# SuperTiny-REV2-Corrected-Stencil.net
KiCad netlist of a schematic drawn in EAGLE
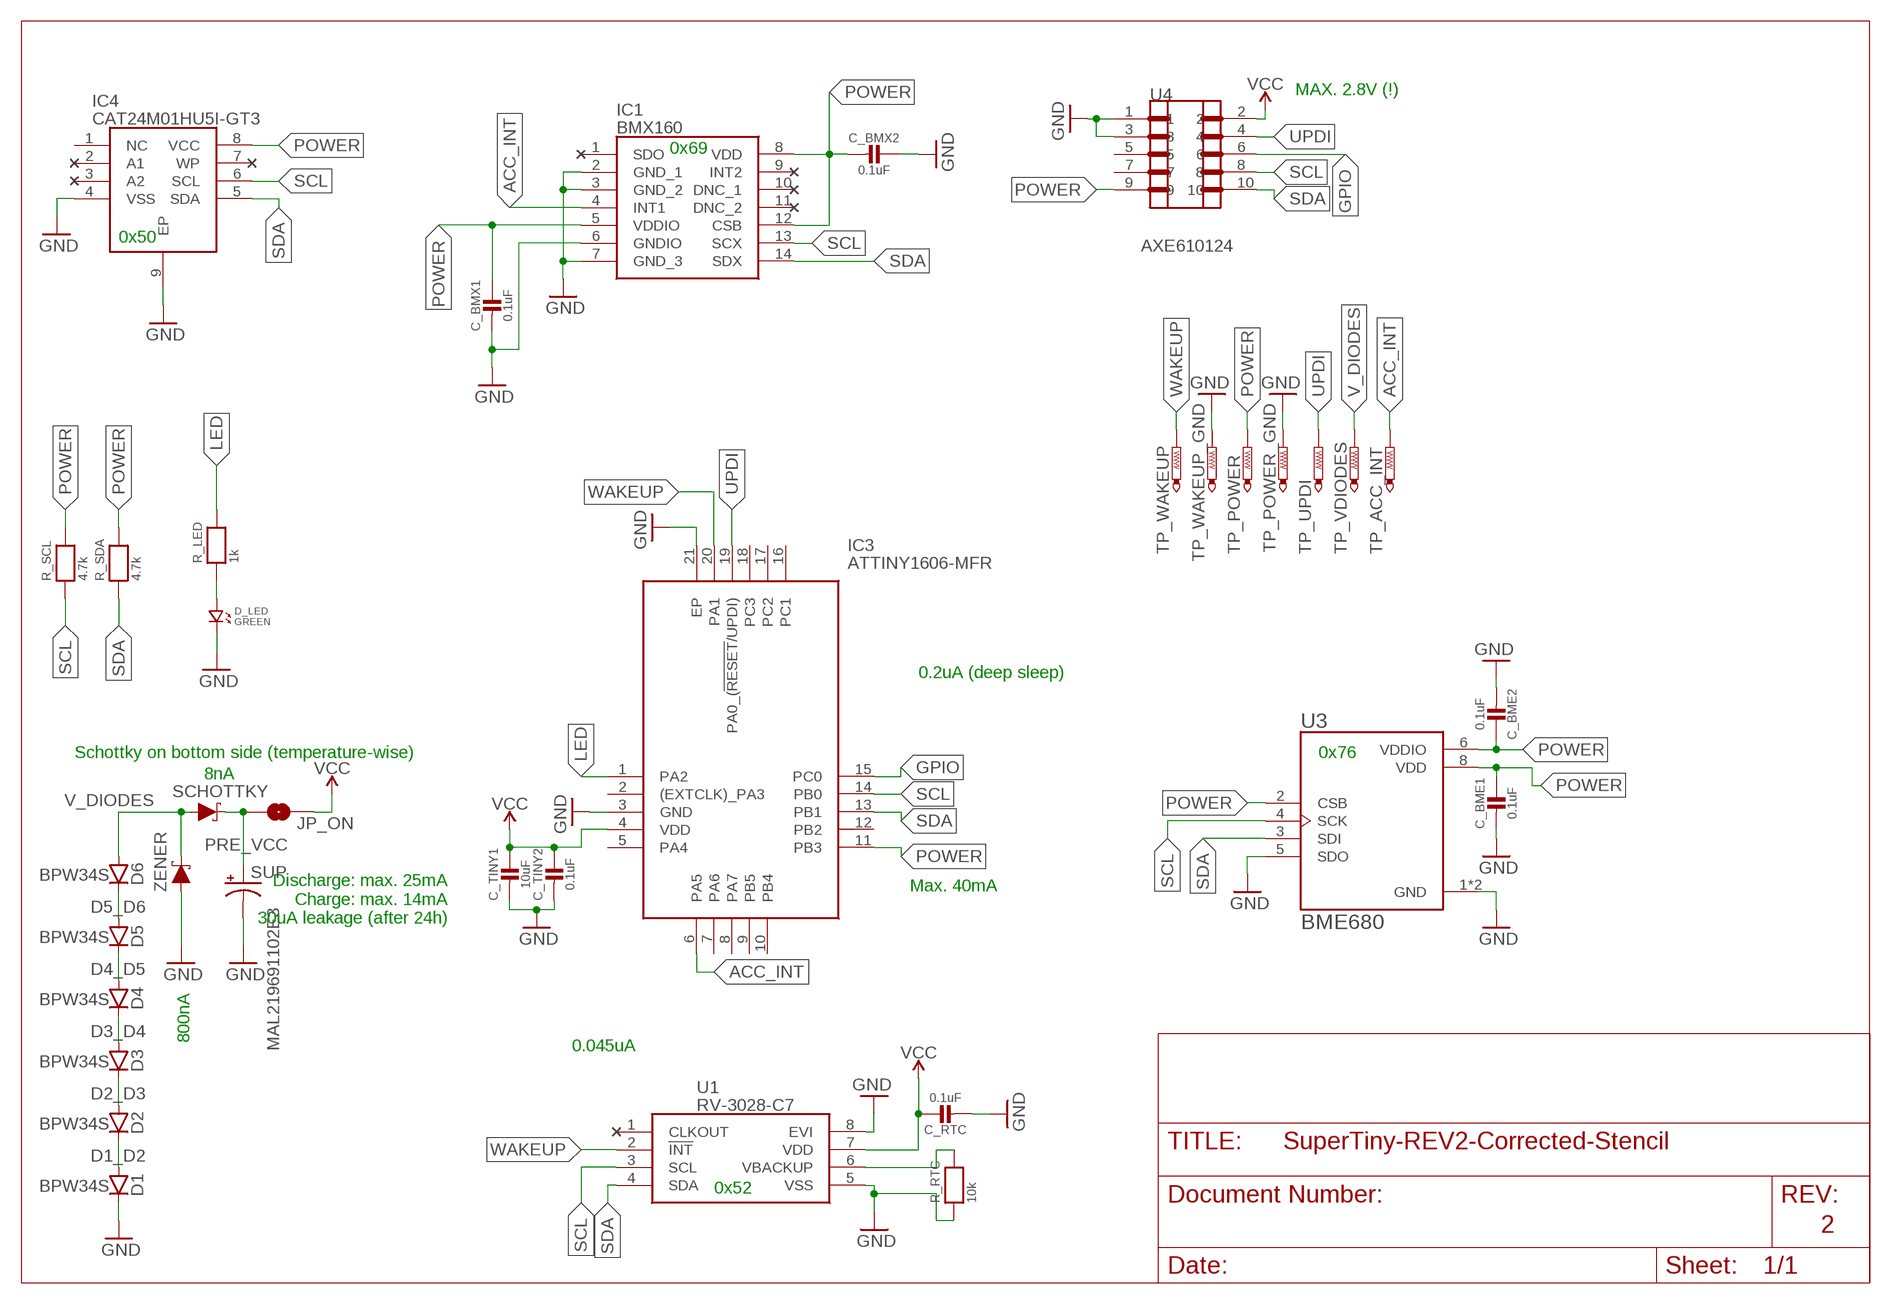
[diagram p0: schematic, sheet 1]

(export (version "E")
  (design (tool "Eeschema 10.0.6"))
  (components
    (comp (ref "C_BME1")
      (value "0.1uF")
      (footprint "eagle-import:MICROBUILDER__0402MP")
      (libsource (lib "eagle-import") (part "MICROBUILDER_CAP_CERAMIC_0402MP"))
    )
    (comp (ref "C_BME2")
      (value "0.1uF")
      (footprint "eagle-import:MICROBUILDER__0402MP")
      (libsource (lib "eagle-import") (part "MICROBUILDER_CAP_CERAMIC_0402MP"))
    )
    (comp (ref "C_BMX1")
      (value "0.1uF")
      (footprint "eagle-import:MICROBUILDER__0402MP")
      (fields (field (name "SPICEPREFIX") "C"))
      (libsource (lib "eagle-import") (part "MICROBUILDER_CAP_CERAMIC_0402MP"))
    )
    (comp (ref "C_BMX2")
      (value "0.1uF")
      (footprint "eagle-import:MICROBUILDER__0402MP")
      (fields (field (name "SPICEPREFIX") "C"))
      (libsource (lib "eagle-import") (part "MICROBUILDER_CAP_CERAMIC_0402MP"))
    )
    (comp (ref "C_RTC")
      (value "0.1uF")
      (footprint "eagle-import:MICROBUILDER__0402MP")
      (fields (field (name "SPICEPREFIX") "C"))
      (libsource (lib "eagle-import") (part "MICROBUILDER_CAP_CERAMIC_0402MP"))
    )
    (comp (ref "C_TINY1")
      (value "10uF")
      (footprint "eagle-import:MICROBUILDER__0402MP")
      (libsource (lib "eagle-import") (part "MICROBUILDER_CAP_CERAMIC_0402MP"))
    )
    (comp (ref "C_TINY2")
      (value "0.1uF")
      (footprint "eagle-import:MICROBUILDER__0402MP")
      (libsource (lib "eagle-import") (part "MICROBUILDER_CAP_CERAMIC_0402MP"))
    )
    (comp (ref "D1")
      (value "BPW34S")
      (footprint "eagle-import:BPW34S")
      (libsource (lib "eagle-import") (part "BPW34S"))
    )
    (comp (ref "D2")
      (value "BPW34S")
      (footprint "eagle-import:BPW34S")
      (libsource (lib "eagle-import") (part "BPW34S"))
    )
    (comp (ref "D3")
      (value "BPW34S")
      (footprint "eagle-import:BPW34S")
      (libsource (lib "eagle-import") (part "BPW34S"))
    )
    (comp (ref "D4")
      (value "BPW34S")
      (footprint "eagle-import:BPW34S")
      (libsource (lib "eagle-import") (part "BPW34S"))
    )
    (comp (ref "D5")
      (value "BPW34S")
      (footprint "eagle-import:BPW34S")
      (libsource (lib "eagle-import") (part "BPW34S"))
    )
    (comp (ref "D6")
      (value "BPW34S")
      (footprint "eagle-import:BPW34S")
      (libsource (lib "eagle-import") (part "BPW34S"))
    )
    (comp (ref "D_LED")
      (value "GREEN")
      (footprint "eagle-import:CMONR_STANDARDPARTS_0402.LED")
      (libsource (lib "eagle-import") (part "CMONR_STANDARDPARTS_LED.0402"))
    )
    (comp (ref "IC1")
      (value "BMX160")
      (footprint "eagle-import:PQFN50P300X250X88-14N")
      (fields (field (name "MOUSER_PART_NUMBER") "262-BMX160"))
      (libsource (lib "eagle-import") (part "BMX160"))
    )
    (comp (ref "IC3")
      (value "ATTINY1606-MFR")
      (footprint "eagle-import:QFN40P300X300X90-21N")
      (fields (field (name "MOUSER_PART_NUMBER") "556-ATTINY1606-MFR"))
      (libsource (lib "eagle-import") (part "ATTINY1606-MFR"))
    )
    (comp (ref "IC4")
      (value "CAT24M01HU5I-GT3")
      (footprint "eagle-import:SON50P300X200X55-9N")
      (fields
        (field (name "MOUSER_PART_NUMBER") "863-CAT24M01HU5I-GT3")
        (field (name "RS_PART_NUMBER") "7814831P")
      )
      (libsource (lib "eagle-import") (part "CAT24M01HU5I-GT3"))
    )
    (comp (ref "JP_ON")
      (value "JUMPER-SMT_2_NO_NO-SILK")
      (footprint "eagle-import:SMT-JUMPER_2_NO_NO-SILK")
      (libsource (lib "eagle-import") (part "JUMPER-SMT_2_NO_NO-SILK"))
    )
    (comp (ref "R_LED")
      (value "1k")
      (footprint "eagle-import:MICROBUILDER__0402MP")
      (libsource (lib "eagle-import") (part "MICROBUILDER_RESISTOR_0402MP"))
    )
    (comp (ref "R_RTC")
      (value "10k")
      (footprint "eagle-import:MICROBUILDER__0402MP")
      (libsource (lib "eagle-import") (part "MICROBUILDER_RESISTOR_0402MP"))
    )
    (comp (ref "R_SCL")
      (value "4.7k")
      (footprint "eagle-import:MICROBUILDER__0402MP")
      (libsource (lib "eagle-import") (part "MICROBUILDER_RESISTOR_0402MP"))
    )
    (comp (ref "R_SDA")
      (value "4.7k")
      (footprint "eagle-import:MICROBUILDER__0402MP")
      (libsource (lib "eagle-import") (part "MICROBUILDER_RESISTOR_0402MP"))
    )
    (comp (ref "SCHOTTKY")
      (value "NSR0140P2T5G")
      (footprint "eagle-import:NSR0140P2T5G")
      (libsource (lib "eagle-import") (part "NSR0140P2T5G"))
    )
    (comp (ref "SUP")
      (value "MAL219691102E3")
      (footprint "eagle-import:MAL219691102E3")
      (libsource (lib "eagle-import") (part "MAL219691102E3"))
    )
    (comp (ref "TP_ACC_INT")
      (value "PTR1TP06SQ")
      (footprint "eagle-import:TP06SQ")
      (libsource (lib "eagle-import") (part "PTR1TP06SQ"))
    )
    (comp (ref "TP_POWER")
      (value "PTR1TP06SQ")
      (footprint "eagle-import:TP06SQ")
      (libsource (lib "eagle-import") (part "PTR1TP06SQ"))
    )
    (comp (ref "TP_POWER_GND")
      (value "PTR1TP06SQ")
      (footprint "eagle-import:TP06SQ")
      (libsource (lib "eagle-import") (part "PTR1TP06SQ"))
    )
    (comp (ref "TP_UPDI")
      (value "PTR1TP06SQ")
      (footprint "eagle-import:TP06SQ")
      (libsource (lib "eagle-import") (part "PTR1TP06SQ"))
    )
    (comp (ref "TP_VDIODES")
      (value "PTR1TP06SQ")
      (footprint "eagle-import:TP06SQ")
      (libsource (lib "eagle-import") (part "PTR1TP06SQ"))
    )
    (comp (ref "TP_WAKEUP")
      (value "PTR1TP06SQ")
      (footprint "eagle-import:TP06SQ")
      (libsource (lib "eagle-import") (part "PTR1TP06SQ"))
    )
    (comp (ref "TP_WAKEUP_GND")
      (value "PTR1TP06SQ")
      (footprint "eagle-import:TP06SQ")
      (libsource (lib "eagle-import") (part "PTR1TP06SQ"))
    )
    (comp (ref "U1")
      (value "RV-3028-C7")
      (footprint "eagle-import:RV3028C7")
      (fields (field (name "SPICEPREFIX") "X"))
      (libsource (lib "eagle-import") (part "RV-3028-C7"))
    )
    (comp (ref "U3")
      (value "BME680")
      (footprint "eagle-import:PSON80P300X300X100-8N")
      (fields (field (name "DIGI-KEY_PART_NUMBER") "828-1077-1-ND") (field (name "MF") "Bosch Sensortec"))
      (libsource (lib "eagle-import") (part "BME680"))
    )
    (comp (ref "U4")
      (value "AXE610124")
      (footprint "eagle-import:AXE610124")
      (libsource (lib "eagle-import") (part "AXE610124"))
    )
    (comp (ref "ZENER")
      (value "MMSZ4683T1G")
      (footprint "eagle-import:MMSZ4683T1G")
      (libsource (lib "eagle-import") (part "MMSZ4683T1G"))
    )
  )
  (nets
    (net (code "1") (name "/D1_D2") (class "Default")
      (node (ref "D1") (pin "PLUS") (pinfunction "PLUS_PLUS") (pintype "passive"))
      (node (ref "D2") (pin "MINUS") (pinfunction "MINUS_MINUS") (pintype "passive"))
    )
    (net (code "2") (name "/D2_D3") (class "Default")
      (node (ref "D2") (pin "PLUS") (pinfunction "PLUS_PLUS") (pintype "passive"))
      (node (ref "D3") (pin "MINUS") (pinfunction "MINUS_MINUS") (pintype "passive"))
    )
    (net (code "3") (name "/D3_D4") (class "Default")
      (node (ref "D3") (pin "PLUS") (pinfunction "PLUS_PLUS") (pintype "passive"))
      (node (ref "D4") (pin "MINUS") (pinfunction "MINUS_MINUS") (pintype "passive"))
    )
    (net (code "4") (name "/D4_D5") (class "Default")
      (node (ref "D4") (pin "PLUS") (pinfunction "PLUS_PLUS") (pintype "passive"))
      (node (ref "D5") (pin "MINUS") (pinfunction "MINUS_MINUS") (pintype "passive"))
    )
    (net (code "5") (name "/D5_D6") (class "Default")
      (node (ref "D5") (pin "PLUS") (pinfunction "PLUS_PLUS") (pintype "passive"))
      (node (ref "D6") (pin "MINUS") (pinfunction "MINUS_MINUS") (pintype "passive"))
    )
    (net (code "6") (name "/PRE_VCC") (class "Default")
      (node (ref "JP_ON") (pin "1") (pinfunction "1_1") (pintype "passive"))
      (node (ref "SCHOTTKY") (pin "P$2") (pinfunction "CA_P$2") (pintype "passive"))
      (node (ref "SUP") (pin "PLUS") (pinfunction "+_PLUS") (pintype "passive"))
    )
    (net (code "7") (name "ACC_INT") (class "Default")
      (node (ref "IC1") (pin "4") (pinfunction "INT1_4") (pintype "bidirectional"))
      (node (ref "IC3") (pin "6") (pinfunction "PA5_6") (pintype "bidirectional"))
      (node (ref "TP_ACC_INT") (pin "TP") (pinfunction "TP_TP") (pintype "input"))
    )
    (net (code "8") (name "GND") (class "Default")
      (node (ref "C_BME1") (pin "2") (pinfunction "2_2") (pintype "passive"))
      (node (ref "C_BME2") (pin "2") (pinfunction "2_2") (pintype "passive"))
      (node (ref "C_BMX1") (pin "2") (pinfunction "2_2") (pintype "passive"))
      (node (ref "C_BMX2") (pin "1") (pinfunction "1_1") (pintype "passive"))
      (node (ref "C_RTC") (pin "2") (pinfunction "2_2") (pintype "passive"))
      (node (ref "C_TINY1") (pin "2") (pinfunction "2_2") (pintype "passive"))
      (node (ref "C_TINY2") (pin "2") (pinfunction "2_2") (pintype "passive"))
      (node (ref "D1") (pin "MINUS") (pinfunction "MINUS_MINUS") (pintype "passive"))
      (node (ref "D_LED") (pin "P$2") (pinfunction "2_P$2") (pintype "bidirectional"))
      (node (ref "IC1") (pin "2") (pinfunction "GND_1_2") (pintype "bidirectional"))
      (node (ref "IC1") (pin "3") (pinfunction "GND_2_3") (pintype "bidirectional"))
      (node (ref "IC1") (pin "6") (pinfunction "GNDIO_6") (pintype "bidirectional"))
      (node (ref "IC1") (pin "7") (pinfunction "GND_3_7") (pintype "bidirectional"))
      (node (ref "IC3") (pin "21") (pinfunction "EP_21") (pintype "bidirectional"))
      (node (ref "IC3") (pin "3") (pinfunction "GND_3") (pintype "bidirectional"))
      (node (ref "IC4") (pin "4") (pinfunction "VSS_4") (pintype "power_in"))
      (node (ref "IC4") (pin "9") (pinfunction "EP_9") (pintype "bidirectional"))
      (node (ref "R_RTC") (pin "1") (pinfunction "1_1") (pintype "passive"))
      (node (ref "SUP") (pin "MINUS") (pinfunction "-_MINUS") (pintype "passive"))
      (node (ref "TP_POWER_GND") (pin "TP") (pinfunction "TP_TP") (pintype "input"))
      (node (ref "TP_WAKEUP_GND") (pin "TP") (pinfunction "TP_TP") (pintype "input"))
      (node (ref "U1") (pin "5") (pinfunction "VSS_5") (pintype "bidirectional"))
      (node (ref "U1") (pin "8") (pinfunction "EVI_8") (pintype "bidirectional"))
      (node (ref "U3") (pin "1") (pinfunction "GND_1") (pintype "power_in"))
      (node (ref "U3") (pin "5") (pinfunction "SDO_5") (pintype "bidirectional"))
      (node (ref "U3") (pin "7") (pinfunction "GND_7") (pintype "power_in"))
      (node (ref "U4") (pin "1") (pinfunction "1_1") (pintype "passive"))
      (node (ref "U4") (pin "3") (pinfunction "3_3") (pintype "passive"))
      (node (ref "ZENER") (pin "P$1") (pinfunction "AN_P$1") (pintype "passive"))
    )
    (net (code "9") (name "GPIO") (class "Default")
      (node (ref "IC3") (pin "15") (pinfunction "PC0_15") (pintype "bidirectional"))
      (node (ref "U4") (pin "6") (pinfunction "6_6") (pintype "passive"))
    )
    (net (code "10") (name "LED") (class "Default")
      (node (ref "IC3") (pin "1") (pinfunction "PA2_1") (pintype "bidirectional"))
      (node (ref "R_LED") (pin "2") (pinfunction "2_2") (pintype "passive"))
    )
    (net (code "11") (name "Net-(D_LED-1)") (class "Default")
      (node (ref "D_LED") (pin "P$1") (pinfunction "1_P$1") (pintype "bidirectional"))
      (node (ref "R_LED") (pin "1") (pinfunction "1_1") (pintype "passive"))
    )
    (net (code "12") (name "Net-(U1-VBACKUP)") (class "Default")
      (node (ref "R_RTC") (pin "2") (pinfunction "2_2") (pintype "passive"))
      (node (ref "U1") (pin "6") (pinfunction "VBACKUP_6") (pintype "bidirectional"))
    )
    (net (code "13") (name "POWER") (class "Default")
      (node (ref "C_BME1") (pin "1") (pinfunction "1_1") (pintype "passive"))
      (node (ref "C_BME2") (pin "1") (pinfunction "1_1") (pintype "passive"))
      (node (ref "C_BMX1") (pin "1") (pinfunction "1_1") (pintype "passive"))
      (node (ref "C_BMX2") (pin "2") (pinfunction "2_2") (pintype "passive"))
      (node (ref "IC1") (pin "12") (pinfunction "CSB_12") (pintype "bidirectional"))
      (node (ref "IC1") (pin "5") (pinfunction "VDDIO_5") (pintype "bidirectional"))
      (node (ref "IC1") (pin "8") (pinfunction "VDD_8") (pintype "bidirectional"))
      (node (ref "IC3") (pin "11") (pinfunction "PB3_11") (pintype "bidirectional"))
      (node (ref "IC4") (pin "8") (pinfunction "VCC_8") (pintype "power_in"))
      (node (ref "R_SCL") (pin "2") (pinfunction "2_2") (pintype "passive"))
      (node (ref "R_SDA") (pin "2") (pinfunction "2_2") (pintype "passive"))
      (node (ref "TP_POWER") (pin "TP") (pinfunction "TP_TP") (pintype "input"))
      (node (ref "U3") (pin "2") (pinfunction "CSB_2") (pintype "input"))
      (node (ref "U3") (pin "6") (pinfunction "VDDIO_6") (pintype "power_in"))
      (node (ref "U3") (pin "8") (pinfunction "VDD_8") (pintype "power_in"))
      (node (ref "U4") (pin "9") (pinfunction "9_9") (pintype "passive"))
    )
    (net (code "14") (name "SCL") (class "Default")
      (node (ref "IC1") (pin "13") (pinfunction "SCX_13") (pintype "bidirectional"))
      (node (ref "IC3") (pin "14") (pinfunction "PB0_14") (pintype "bidirectional"))
      (node (ref "IC4") (pin "6") (pinfunction "SCL_6") (pintype "bidirectional"))
      (node (ref "R_SCL") (pin "1") (pinfunction "1_1") (pintype "passive"))
      (node (ref "U1") (pin "3") (pinfunction "SCL_3") (pintype "bidirectional"))
      (node (ref "U3") (pin "4") (pinfunction "SCK_4") (pintype "input"))
      (node (ref "U4") (pin "8") (pinfunction "8_8") (pintype "passive"))
    )
    (net (code "15") (name "SDA") (class "Default")
      (node (ref "IC1") (pin "14") (pinfunction "SDX_14") (pintype "bidirectional"))
      (node (ref "IC3") (pin "13") (pinfunction "PB1_13") (pintype "bidirectional"))
      (node (ref "IC4") (pin "5") (pinfunction "SDA_5") (pintype "bidirectional"))
      (node (ref "R_SDA") (pin "1") (pinfunction "1_1") (pintype "passive"))
      (node (ref "U1") (pin "4") (pinfunction "SDA_4") (pintype "bidirectional"))
      (node (ref "U3") (pin "3") (pinfunction "SDI_3") (pintype "bidirectional"))
      (node (ref "U4") (pin "10") (pinfunction "10_10") (pintype "passive"))
    )
    (net (code "16") (name "UPDI") (class "Default")
      (node (ref "IC3") (pin "19") (pinfunction "PA0_(~{RESET}/UPDI)_19") (pintype "bidirectional"))
      (node (ref "TP_UPDI") (pin "TP") (pinfunction "TP_TP") (pintype "input"))
      (node (ref "U4") (pin "4") (pinfunction "4_4") (pintype "passive"))
    )
    (net (code "17") (name "VCC") (class "Default")
      (node (ref "C_RTC") (pin "1") (pinfunction "1_1") (pintype "passive"))
      (node (ref "C_TINY1") (pin "1") (pinfunction "1_1") (pintype "passive"))
      (node (ref "C_TINY2") (pin "1") (pinfunction "1_1") (pintype "passive"))
      (node (ref "IC3") (pin "4") (pinfunction "VDD_4") (pintype "bidirectional"))
      (node (ref "JP_ON") (pin "2") (pinfunction "2_2") (pintype "passive"))
      (node (ref "U1") (pin "7") (pinfunction "VDD_7") (pintype "bidirectional"))
      (node (ref "U4") (pin "2") (pinfunction "2_2") (pintype "passive"))
    )
    (net (code "18") (name "V_DIODES") (class "Default")
      (node (ref "D6") (pin "PLUS") (pinfunction "PLUS_PLUS") (pintype "passive"))
      (node (ref "SCHOTTKY") (pin "P$1") (pinfunction "AN_P$1") (pintype "passive"))
      (node (ref "TP_VDIODES") (pin "TP") (pinfunction "TP_TP") (pintype "input"))
      (node (ref "ZENER") (pin "P$2") (pinfunction "CA_P$2") (pintype "passive"))
    )
    (net (code "19") (name "WAKEUP") (class "Default")
      (node (ref "IC3") (pin "20") (pinfunction "PA1_20") (pintype "bidirectional"))
      (node (ref "TP_WAKEUP") (pin "TP") (pinfunction "TP_TP") (pintype "input"))
      (node (ref "U1") (pin "2") (pinfunction "~{INT}_2") (pintype "bidirectional"))
    )
    (net (code "20") (name "unconnected-(IC1-DNC_1-Pad10)") (class "Default")
      (node (ref "IC1") (pin "10") (pinfunction "DNC_1_10") (pintype "bidirectional"))
    )
    (net (code "21") (name "unconnected-(IC1-DNC_2-Pad11)") (class "Default")
      (node (ref "IC1") (pin "11") (pinfunction "DNC_2_11") (pintype "bidirectional"))
    )
    (net (code "22") (name "unconnected-(IC1-INT2-Pad9)") (class "Default")
      (node (ref "IC1") (pin "9") (pinfunction "INT2_9") (pintype "bidirectional"))
    )
    (net (code "23") (name "unconnected-(IC1-SDO-Pad1)") (class "Default")
      (node (ref "IC1") (pin "1") (pinfunction "SDO_1") (pintype "bidirectional"))
    )
    (net (code "24") (name "unconnected-(IC3-(EXTCLK)_PA3-Pad2)") (class "Default")
      (node (ref "IC3") (pin "2") (pinfunction "(EXTCLK)_PA3_2") (pintype "bidirectional"))
    )
    (net (code "25") (name "unconnected-(IC3-PA4-Pad5)") (class "Default")
      (node (ref "IC3") (pin "5") (pinfunction "PA4_5") (pintype "bidirectional"))
    )
    (net (code "26") (name "unconnected-(IC3-PA6-Pad7)") (class "Default")
      (node (ref "IC3") (pin "7") (pinfunction "PA6_7") (pintype "bidirectional"))
    )
    (net (code "27") (name "unconnected-(IC3-PA7-Pad8)") (class "Default")
      (node (ref "IC3") (pin "8") (pinfunction "PA7_8") (pintype "bidirectional"))
    )
    (net (code "28") (name "unconnected-(IC3-PB2-Pad12)") (class "Default")
      (node (ref "IC3") (pin "12") (pinfunction "PB2_12") (pintype "bidirectional"))
    )
    (net (code "29") (name "unconnected-(IC3-PB4-Pad10)") (class "Default")
      (node (ref "IC3") (pin "10") (pinfunction "PB4_10") (pintype "bidirectional"))
    )
    (net (code "30") (name "unconnected-(IC3-PB5-Pad9)") (class "Default")
      (node (ref "IC3") (pin "9") (pinfunction "PB5_9") (pintype "bidirectional"))
    )
    (net (code "31") (name "unconnected-(IC3-PC1-Pad16)") (class "Default")
      (node (ref "IC3") (pin "16") (pinfunction "PC1_16") (pintype "bidirectional"))
    )
    (net (code "32") (name "unconnected-(IC3-PC2-Pad17)") (class "Default")
      (node (ref "IC3") (pin "17") (pinfunction "PC2_17") (pintype "bidirectional"))
    )
    (net (code "33") (name "unconnected-(IC3-PC3-Pad18)") (class "Default")
      (node (ref "IC3") (pin "18") (pinfunction "PC3_18") (pintype "bidirectional"))
    )
    (net (code "34") (name "unconnected-(IC4-A1-Pad2)") (class "Default")
      (node (ref "IC4") (pin "2") (pinfunction "A1_2") (pintype "bidirectional"))
    )
    (net (code "35") (name "unconnected-(IC4-A2-Pad3)") (class "Default")
      (node (ref "IC4") (pin "3") (pinfunction "A2_3") (pintype "bidirectional"))
    )
    (net (code "36") (name "unconnected-(IC4-NC-Pad1)") (class "Default")
      (node (ref "IC4") (pin "1") (pinfunction "NC_1") (pintype "no_connect"))
    )
    (net (code "37") (name "unconnected-(IC4-WP-Pad7)") (class "Default")
      (node (ref "IC4") (pin "7") (pinfunction "WP_7") (pintype "bidirectional"))
    )
    (net (code "38") (name "unconnected-(U1-CLKOUT-Pad1)") (class "Default")
      (node (ref "U1") (pin "1") (pinfunction "CLKOUT_1") (pintype "bidirectional"))
    )
    (net (code "39") (name "unconnected-(U4-Pad5)") (class "Default")
      (node (ref "U4") (pin "5") (pinfunction "5_5") (pintype "passive"))
    )
    (net (code "40") (name "unconnected-(U4-Pad7)") (class "Default")
      (node (ref "U4") (pin "7") (pinfunction "7_7") (pintype "passive"))
    )
  )
)
